# CO2SN.net
KiCad netlist of a schematic drawn in EAGLE
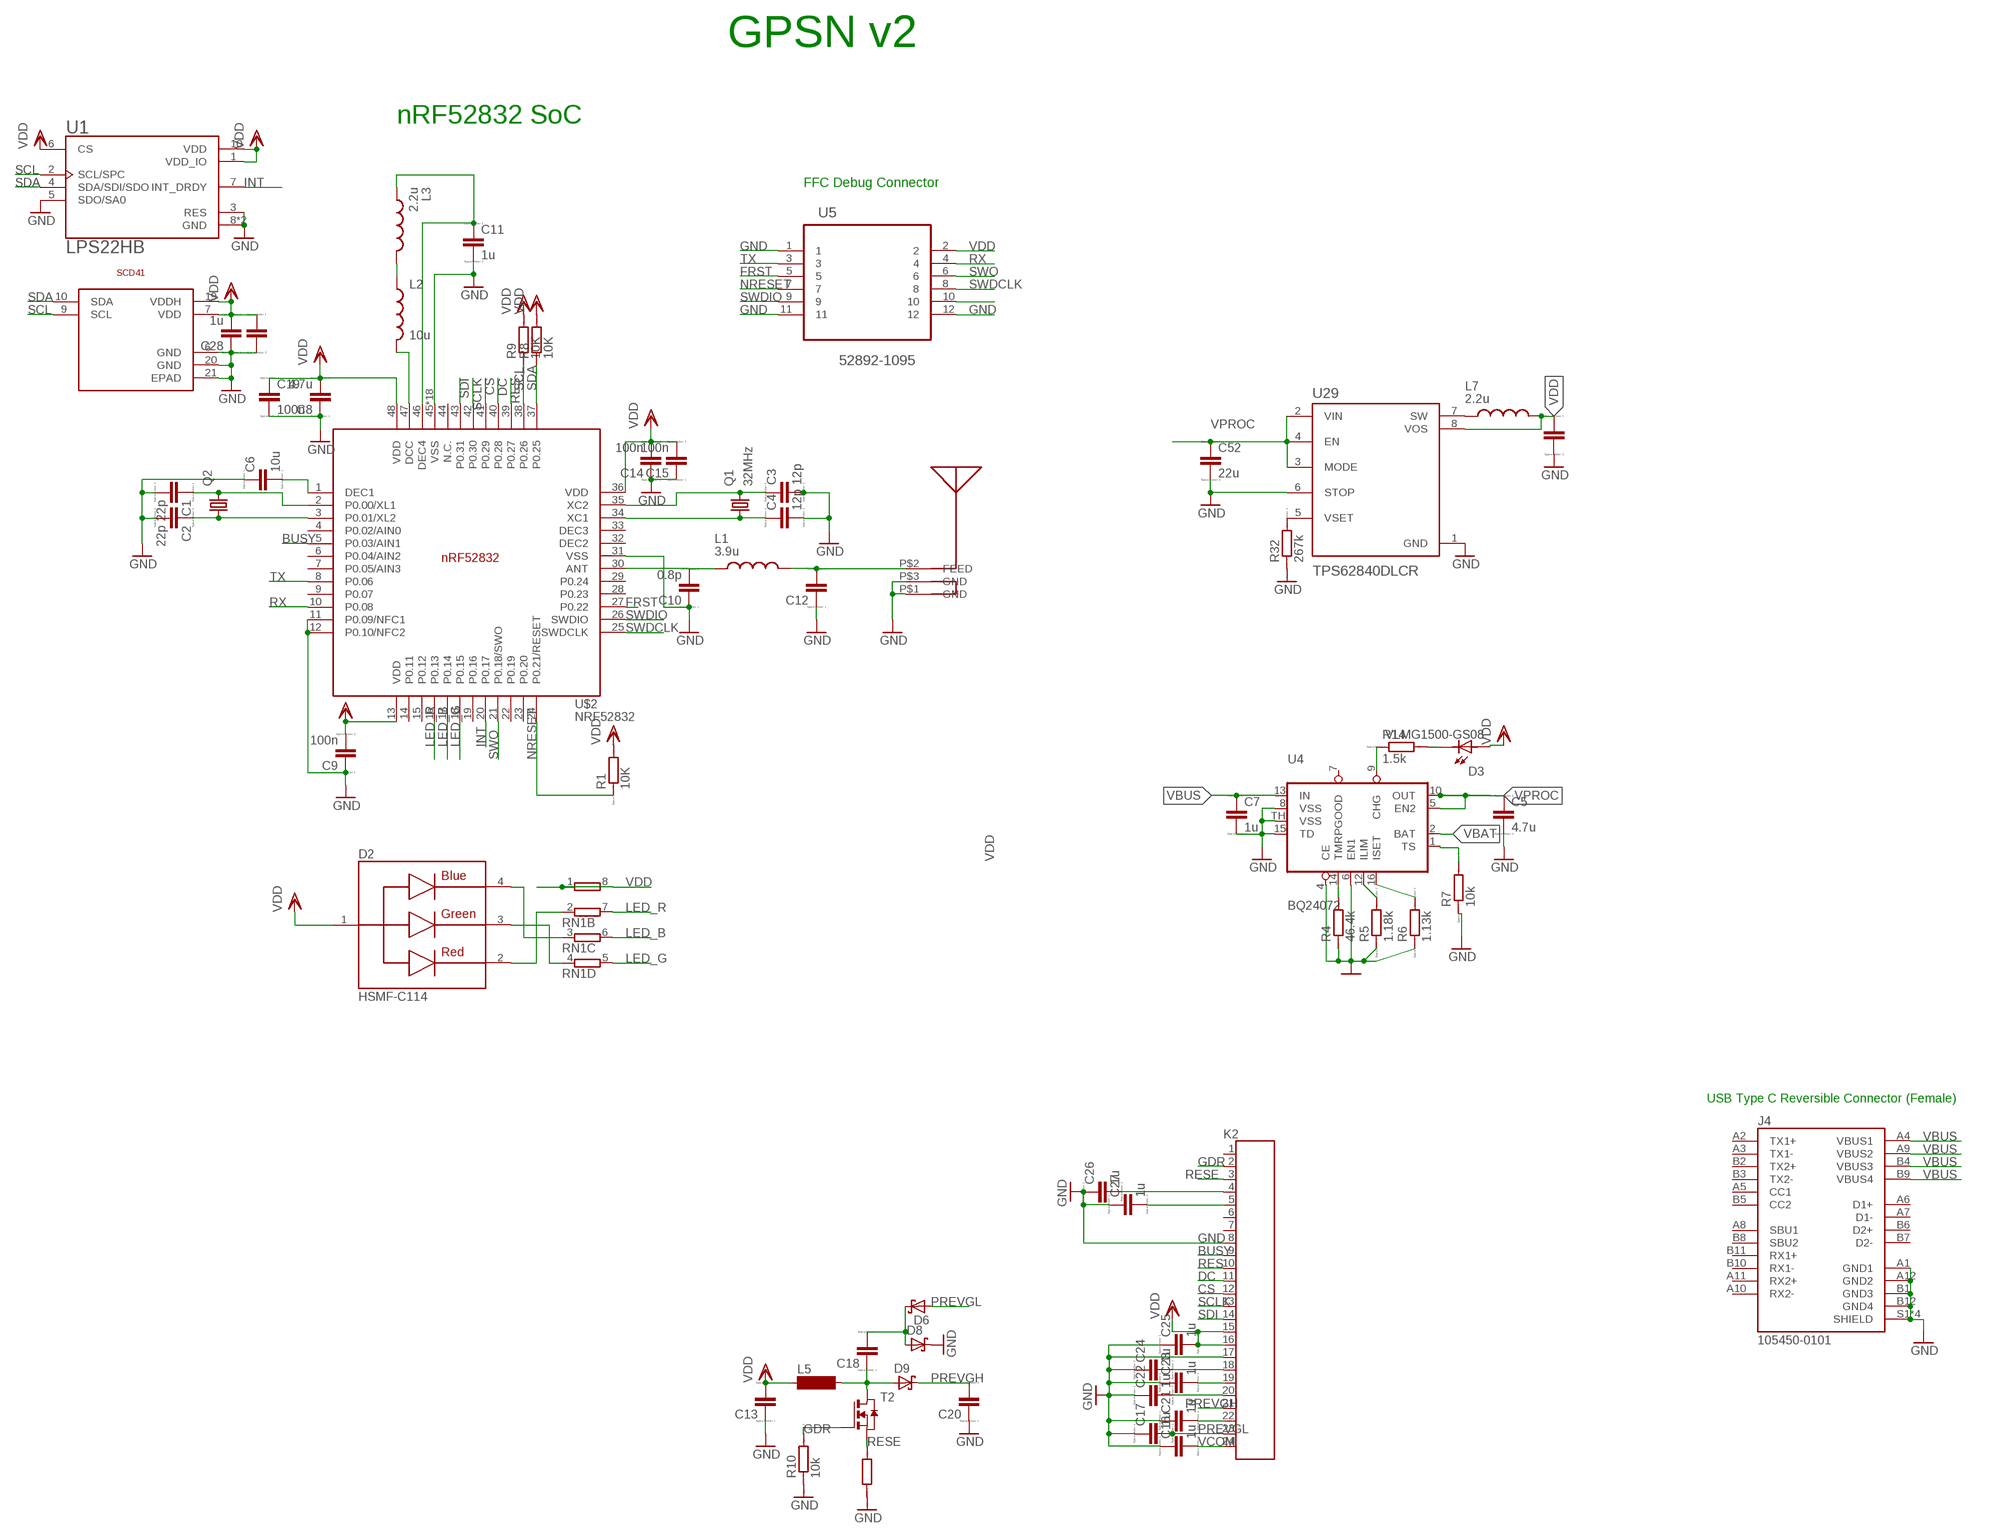
[diagram p0: schematic, sheet 1]

(export (version "E")
  (design (tool "Eeschema 10.0.6"))
  (components
    (comp (ref "C1")
      (value "22p")
      (footprint "eagle-import:C0402")
      (libsource (lib "eagle-import") (part "CC0402"))
    )
    (comp (ref "C2")
      (value "22p")
      (footprint "eagle-import:C0402")
      (libsource (lib "eagle-import") (part "CC0402"))
    )
    (comp (ref "C3")
      (value "12p")
      (footprint "eagle-import:C0402")
      (libsource (lib "eagle-import") (part "CC0402"))
    )
    (comp (ref "C4")
      (value "12p")
      (footprint "eagle-import:C0402")
      (libsource (lib "eagle-import") (part "CC0402"))
    )
    (comp (ref "C5")
      (value "4.7u")
      (footprint "eagle-import:C0402")
      (libsource (lib "eagle-import") (part "CC0402"))
    )
    (comp (ref "C6")
      (value "10u")
      (footprint "eagle-import:C0402")
      (libsource (lib "eagle-import") (part "CC0402"))
    )
    (comp (ref "C7")
      (value "1u")
      (footprint "eagle-import:C0402")
      (libsource (lib "eagle-import") (part "CC0402"))
    )
    (comp (ref "C8")
      (value "4.7u")
      (footprint "eagle-import:C0402")
      (libsource (lib "eagle-import") (part "CC0402"))
    )
    (comp (ref "C9")
      (value "100n")
      (footprint "eagle-import:C0603R")
      (libsource (lib "eagle-import") (part "CC0603R"))
    )
    (comp (ref "C10")
      (value "0.8p")
      (footprint "eagle-import:C0402")
      (libsource (lib "eagle-import") (part "CC0402"))
    )
    (comp (ref "C11")
      (value "1u")
      (footprint "eagle-import:C0402")
      (libsource (lib "eagle-import") (part "CC0402"))
    )
    (comp (ref "C12")
      (value "1.2p")
      (footprint "eagle-import:C0402")
      (libsource (lib "eagle-import") (part "CC0402"))
    )
    (comp (ref "C13")
      (value "100n")
      (footprint "eagle-import:C0603R")
      (libsource (lib "eagle-import") (part "CC0603R"))
    )
    (comp (ref "C14")
      (value "100n")
      (footprint "eagle-import:C0402")
      (libsource (lib "eagle-import") (part "CC0402"))
    )
    (comp (ref "C15")
      (value "100n")
      (footprint "eagle-import:C0402")
      (libsource (lib "eagle-import") (part "CC0402"))
    )
    (comp (ref "C16")
      (value "1u")
      (footprint "eagle-import:C0402")
      (libsource (lib "eagle-import") (part "CC0402"))
    )
    (comp (ref "C17")
      (value "1u")
      (footprint "eagle-import:C0402")
      (libsource (lib "eagle-import") (part "CC0402"))
    )
    (comp (ref "C18")
      (value "100n")
      (footprint "eagle-import:C0603R")
      (libsource (lib "eagle-import") (part "CC0603R"))
    )
    (comp (ref "C19")
      (value "100n")
      (footprint "eagle-import:C0402")
      (libsource (lib "eagle-import") (part "CC0402"))
    )
    (comp (ref "C20")
      (value "100n")
      (footprint "eagle-import:C0603R")
      (libsource (lib "eagle-import") (part "CC0603R"))
    )
    (comp (ref "C21")
      (value "1u")
      (footprint "eagle-import:C0402")
      (libsource (lib "eagle-import") (part "CC0402"))
    )
    (comp (ref "C22")
      (value "1u")
      (footprint "eagle-import:C0402")
      (libsource (lib "eagle-import") (part "CC0402"))
    )
    (comp (ref "C23")
      (value "1u")
      (footprint "eagle-import:C0402")
      (libsource (lib "eagle-import") (part "CC0402"))
    )
    (comp (ref "C24")
      (value "1u")
      (footprint "eagle-import:C0402")
      (libsource (lib "eagle-import") (part "CC0402"))
    )
    (comp (ref "C25")
      (value "1u")
      (footprint "eagle-import:C0402")
      (libsource (lib "eagle-import") (part "CC0402"))
    )
    (comp (ref "C26")
      (value "1u")
      (footprint "eagle-import:C0402")
      (libsource (lib "eagle-import") (part "CC0402"))
    )
    (comp (ref "C27")
      (value "1u")
      (footprint "eagle-import:C0402")
      (libsource (lib "eagle-import") (part "CC0402"))
    )
    (comp (ref "C28")
      (value "1u")
      (footprint "eagle-import:C0402")
      (libsource (lib "eagle-import") (part "CC0402"))
    )
    (comp (ref "C29")
      (value "22u")
      (footprint "eagle-import:C0603R")
      (libsource (lib "eagle-import") (part "CC0603R"))
    )
    (comp (ref "C52")
      (value "22u")
      (footprint "eagle-import:C0603R")
      (libsource (lib "eagle-import") (part "CC0603R"))
    )
    (comp (ref "C58")
      (value "22u")
      (footprint "eagle-import:C0603R")
      (libsource (lib "eagle-import") (part "CC0603R"))
    )
    (comp (ref "D2")
      (value "HSMF-C114")
      (footprint "eagle-import:DIOSC160X150X35-4N")
      (fields (field (name "MF") "Broadcom Limited"))
      (libsource (lib "eagle-import") (part "HSMF-C114"))
    )
    (comp (ref "D3")
      (value "VLMG1500-GS08")
      (footprint "eagle-import:LEDC1005X35N")
      (fields (field (name "MF") "Vishay"))
      (libsource (lib "eagle-import") (part "VLMG1500-GS08"))
    )
    (comp (ref "D6")
      (value "1PS79SB30,115")
      (footprint "eagle-import:SOD523")
      (fields (field (name "MF") "Nexperia"))
      (libsource (lib "eagle-import") (part "1PS79SB30,115"))
    )
    (comp (ref "D8")
      (value "1PS79SB30,115")
      (footprint "eagle-import:SOD523")
      (fields (field (name "MF") "Nexperia"))
      (libsource (lib "eagle-import") (part "1PS79SB30,115"))
    )
    (comp (ref "D9")
      (value "1PS79SB30,115")
      (footprint "eagle-import:SOD523")
      (fields (field (name "MF") "Nexperia"))
      (libsource (lib "eagle-import") (part "1PS79SB30,115"))
    )
    (comp (ref "J4")
      (value "105450-0101")
      (footprint "eagle-import:MOLEX_105450-0101")
      (fields (field (name "MF") "Molex") (field (name "MP") "1054500101"))
      (libsource (lib "eagle-import") (part "105450-0101"))
    )
    (comp (ref "K2")
      (value "687124149022")
      (footprint "eagle-import:687124149022")
      (fields (field (name "MF") "Wurth Electronics"))
      (libsource (lib "eagle-import") (part "687124149022"))
    )
    (comp (ref "L1")
      (value "3.9u")
      (footprint "eagle-import:INDC0402X26N")
      (fields (field (name "MF") "TDK") (field (name "MP") "MHQ0402P7N5JT000"))
      (libsource (lib "eagle-import") (part "MHQ0402P7N5JT000"))
    )
    (comp (ref "L2")
      (value "10u")
      (footprint "eagle-import:L0603")
      (libsource (lib "eagle-import") (part "INDUCTOR"))
    )
    (comp (ref "L3")
      (value "2.2u")
      (footprint "eagle-import:INDC0402X26N")
      (fields (field (name "MF") "TDK") (field (name "MP") "MHQ0402P7N5JT000"))
      (libsource (lib "eagle-import") (part "MHQ0402P7N5JT000"))
    )
    (comp (ref "L5")
      (value "SM-NE29")
      (footprint "eagle-import:SM-NE29")
      (libsource (lib "eagle-import") (part "SM-NE29"))
    )
    (comp (ref "L7")
      (value "2.2u")
      (footprint "eagle-import:INDC3225X120N")
      (fields (field (name "MF") "Murata") (field (name "MP") "1277AS-H-1R5M=P2"))
      (libsource (lib "eagle-import") (part "1277AS-H-1R5M=P2"))
    )
    (comp (ref "Q1")
      (value "32MHz")
      (footprint "eagle-import:2.0X1.6_KX-5")
      (libsource (lib "eagle-import") (part "KX-5"))
    )
    (comp (ref "Q2")
      (value "KX-327-RT")
      (footprint "eagle-import:2.0X1.2")
      (libsource (lib "eagle-import") (part "KX-327-RT"))
    )
    (comp (ref "R1")
      (value "10K")
      (footprint "eagle-import:R0402")
      (libsource (lib "eagle-import") (part "RR0402"))
    )
    (comp (ref "R4")
      (value "46.4k")
      (footprint "eagle-import:R0402")
      (libsource (lib "eagle-import") (part "RR0402"))
    )
    (comp (ref "R5")
      (value "1.18k")
      (footprint "eagle-import:R0402")
      (libsource (lib "eagle-import") (part "RR0402"))
    )
    (comp (ref "R6")
      (value "1.13k")
      (footprint "eagle-import:R0402")
      (libsource (lib "eagle-import") (part "RR0402"))
    )
    (comp (ref "R7")
      (value "10k")
      (footprint "eagle-import:R0402")
      (libsource (lib "eagle-import") (part "RR0402"))
    )
    (comp (ref "R8")
      (value "10K")
      (footprint "eagle-import:R0402")
      (libsource (lib "eagle-import") (part "RR0402"))
    )
    (comp (ref "R9")
      (value "10K")
      (footprint "eagle-import:R0402")
      (libsource (lib "eagle-import") (part "RR0402"))
    )
    (comp (ref "R10")
      (value "10k")
      (footprint "eagle-import:R0402")
      (libsource (lib "eagle-import") (part "RR0402"))
    )
    (comp (ref "R11")
      (value "0.47")
      (footprint "eagle-import:R0402")
      (libsource (lib "eagle-import") (part "RR0402"))
    )
    (comp (ref "R14")
      (value "1.5k")
      (footprint "eagle-import:R0402")
      (libsource (lib "eagle-import") (part "RR0402"))
    )
    (comp (ref "R32")
      (value "267k")
      (footprint "eagle-import:R0402")
      (libsource (lib "eagle-import") (part "RR0402"))
    )
    (comp (ref "RN1")
      (value "4R-N0402ARV341")
      (footprint "eagle-import:4X0402ARV341")
      (libsource (lib "eagle-import") (part "4R-N0402ARV341"))
    )
    (comp (ref "T2")
      (value "NMOSSOT23")
      (footprint "eagle-import:SOT-23")
      (libsource (lib "eagle-import") (part "NMOSSOT23"))
    )
    (comp (ref "U$1")
      (value "SCD41")
      (footprint "eagle-import:SCD41")
      (libsource (lib "eagle-import") (part "SCD41"))
    )
    (comp (ref "U$2")
      (value "NRF52832")
      (footprint "eagle-import:QFN40P600X600X90-48_N")
      (libsource (lib "eagle-import") (part "NRF52832"))
    )
    (comp (ref "U$4")
      (value "CHIPANTENNAL2")
      (footprint "eagle-import:CHIPANTENNAL2")
      (libsource (lib "eagle-import") (part "CHIPANTENNAL2"))
    )
    (comp (ref "U1")
      (value "LPS22HB")
      (footprint "eagle-import:LGA10R50P2X3_200X200X80")
      (fields (field (name "MF") "STMicroelectronics"))
      (libsource (lib "eagle-import") (part "LPS22HB"))
    )
    (comp (ref "U4")
      (value "BQ24072")
      (footprint "eagle-import:S-PVQFN-N16")
      (libsource (lib "eagle-import") (part "BQ24072"))
    )
    (comp (ref "U5")
      (value "52892-1095")
      (footprint "eagle-import:MOLEX_52892-1095")
      (fields (field (name "MF") "Molex"))
      (libsource (lib "eagle-import") (part "52892-1095"))
    )
    (comp (ref "U29")
      (value "TPS62840DLCR")
      (footprint "eagle-import:SON50P200X150X100-8N")
      (fields (field (name "MF") "Texas Instruments"))
      (libsource (lib "eagle-import") (part "TPS62840DLCR"))
    )
  )
  (nets
    (net (code "1") (name "/BUSY") (class "Default")
      (node (ref "K2") (pin "9") (pinfunction "9_9") (pintype "passive"))
      (node (ref "U$2") (pin "5") (pinfunction "P0.03/AIN1_5") (pintype "bidirectional"))
    )
    (net (code "2") (name "/CS") (class "Default")
      (node (ref "K2") (pin "12") (pinfunction "12_12") (pintype "passive"))
      (node (ref "U$2") (pin "41") (pinfunction "P0.29_41") (pintype "bidirectional"))
    )
    (net (code "3") (name "/DC") (class "Default")
      (node (ref "K2") (pin "11") (pinfunction "11_11") (pintype "passive"))
      (node (ref "U$2") (pin "40") (pinfunction "P0.28_40") (pintype "bidirectional"))
    )
    (net (code "4") (name "/FRST") (class "Default")
      (node (ref "U$2") (pin "27") (pinfunction "P0.22_27") (pintype "bidirectional"))
      (node (ref "U5") (pin "5") (pinfunction "5_5") (pintype "passive"))
    )
    (net (code "5") (name "/GDR") (class "Default")
      (node (ref "K2") (pin "2") (pinfunction "2_2") (pintype "passive"))
      (node (ref "R10") (pin "2") (pinfunction "2_2") (pintype "passive"))
      (node (ref "T2") (pin "3") (pinfunction "G_3") (pintype "passive"))
    )
    (net (code "6") (name "/INT") (class "Default")
      (node (ref "U$2") (pin "20") (pinfunction "P0.17_20") (pintype "bidirectional"))
      (node (ref "U1") (pin "7") (pinfunction "INT_DRDY_7") (pintype "output"))
    )
    (net (code "7") (name "/LED_B") (class "Default")
      (node (ref "RN1") (pin "6") (pinfunction "2_6") (pintype "passive"))
      (node (ref "U$2") (pin "17") (pinfunction "P0.14_17") (pintype "bidirectional"))
    )
    (net (code "8") (name "/LED_G") (class "Default")
      (node (ref "RN1") (pin "5") (pinfunction "2_5") (pintype "passive"))
      (node (ref "U$2") (pin "18") (pinfunction "P0.15_18") (pintype "bidirectional"))
    )
    (net (code "9") (name "/LED_R") (class "Default")
      (node (ref "RN1") (pin "7") (pinfunction "2_7") (pintype "passive"))
      (node (ref "U$2") (pin "16") (pinfunction "P0.13_16") (pintype "bidirectional"))
    )
    (net (code "10") (name "/NRESET") (class "Default")
      (node (ref "R1") (pin "1") (pinfunction "1_1") (pintype "passive"))
      (node (ref "U$2") (pin "24") (pinfunction "P0.21/RESET_24") (pintype "bidirectional"))
      (node (ref "U5") (pin "7") (pinfunction "7_7") (pintype "passive"))
    )
    (net (code "11") (name "/PREVGH") (class "Default")
      (node (ref "C20") (pin "2") (pinfunction "2_2") (pintype "passive"))
      (node (ref "D9") (pin "1") (pinfunction "K_1") (pintype "passive"))
      (node (ref "K2") (pin "21") (pinfunction "21_21") (pintype "passive"))
    )
    (net (code "12") (name "/PREVGL") (class "Default")
      (node (ref "C17") (pin "2") (pinfunction "2_2") (pintype "passive"))
      (node (ref "D6") (pin "2") (pinfunction "A_2") (pintype "passive"))
      (node (ref "K2") (pin "23") (pinfunction "23_23") (pintype "passive"))
    )
    (net (code "13") (name "/RES") (class "Default")
      (node (ref "K2") (pin "10") (pinfunction "10_10") (pintype "passive"))
      (node (ref "U$2") (pin "39") (pinfunction "P0.27_39") (pintype "bidirectional"))
    )
    (net (code "14") (name "/RESE") (class "Default")
      (node (ref "K2") (pin "3") (pinfunction "3_3") (pintype "passive"))
      (node (ref "R11") (pin "2") (pinfunction "2_2") (pintype "passive"))
      (node (ref "T2") (pin "2") (pinfunction "S_2") (pintype "passive"))
    )
    (net (code "15") (name "/RX") (class "Default")
      (node (ref "U$2") (pin "10") (pinfunction "P0.08_10") (pintype "bidirectional"))
      (node (ref "U5") (pin "4") (pinfunction "4_4") (pintype "passive"))
    )
    (net (code "16") (name "/SCL") (class "Default")
      (node (ref "R9") (pin "1") (pinfunction "1_1") (pintype "passive"))
      (node (ref "U$1") (pin "9") (pinfunction "SCL_9") (pintype "bidirectional"))
      (node (ref "U$2") (pin "38") (pinfunction "P0.26_38") (pintype "bidirectional"))
      (node (ref "U1") (pin "2") (pinfunction "SCL/SPC_2") (pintype "input"))
    )
    (net (code "17") (name "/SCLK") (class "Default")
      (node (ref "K2") (pin "13") (pinfunction "13_13") (pintype "passive"))
      (node (ref "U$2") (pin "42") (pinfunction "P0.30_42") (pintype "bidirectional"))
    )
    (net (code "18") (name "/SDA") (class "Default")
      (node (ref "R8") (pin "1") (pinfunction "1_1") (pintype "passive"))
      (node (ref "U$1") (pin "10") (pinfunction "SDA_10") (pintype "bidirectional"))
      (node (ref "U$2") (pin "37") (pinfunction "P0.25_37") (pintype "bidirectional"))
      (node (ref "U1") (pin "4") (pinfunction "SDA/SDI/SDO_4") (pintype "bidirectional"))
    )
    (net (code "19") (name "/SDI") (class "Default")
      (node (ref "K2") (pin "14") (pinfunction "14_14") (pintype "passive"))
      (node (ref "U$2") (pin "43") (pinfunction "P0.31_43") (pintype "bidirectional"))
    )
    (net (code "20") (name "/SWDCLK") (class "Default")
      (node (ref "U$2") (pin "25") (pinfunction "SWDCLK_25") (pintype "input"))
      (node (ref "U5") (pin "8") (pinfunction "8_8") (pintype "passive"))
    )
    (net (code "21") (name "/SWDIO") (class "Default")
      (node (ref "U$2") (pin "26") (pinfunction "SWDIO_26") (pintype "bidirectional"))
      (node (ref "U5") (pin "9") (pinfunction "9_9") (pintype "passive"))
    )
    (net (code "22") (name "/SWO") (class "Default")
      (node (ref "U$2") (pin "21") (pinfunction "P0.18/SWO_21") (pintype "bidirectional"))
      (node (ref "U5") (pin "6") (pinfunction "6_6") (pintype "passive"))
    )
    (net (code "23") (name "/TX") (class "Default")
      (node (ref "U$2") (pin "8") (pinfunction "P0.06_8") (pintype "bidirectional"))
      (node (ref "U5") (pin "3") (pinfunction "3_3") (pintype "passive"))
    )
    (net (code "24") (name "/VCOM") (class "Default")
      (node (ref "C16") (pin "2") (pinfunction "2_2") (pintype "passive"))
      (node (ref "K2") (pin "24") (pinfunction "24_24") (pintype "passive"))
    )
    (net (code "25") (name "GND") (class "Default")
      (node (ref "C1") (pin "2") (pinfunction "2_2") (pintype "passive"))
      (node (ref "C10") (pin "1") (pinfunction "1_1") (pintype "passive"))
      (node (ref "C11") (pin "2") (pinfunction "2_2") (pintype "passive"))
      (node (ref "C12") (pin "1") (pinfunction "1_1") (pintype "passive"))
      (node (ref "C13") (pin "1") (pinfunction "1_1") (pintype "passive"))
      (node (ref "C14") (pin "1") (pinfunction "1_1") (pintype "passive"))
      (node (ref "C15") (pin "1") (pinfunction "1_1") (pintype "passive"))
      (node (ref "C16") (pin "1") (pinfunction "1_1") (pintype "passive"))
      (node (ref "C17") (pin "1") (pinfunction "1_1") (pintype "passive"))
      (node (ref "C19") (pin "2") (pinfunction "2_2") (pintype "passive"))
      (node (ref "C2") (pin "2") (pinfunction "2_2") (pintype "passive"))
      (node (ref "C20") (pin "1") (pinfunction "1_1") (pintype "passive"))
      (node (ref "C21") (pin "1") (pinfunction "1_1") (pintype "passive"))
      (node (ref "C22") (pin "1") (pinfunction "1_1") (pintype "passive"))
      (node (ref "C23") (pin "1") (pinfunction "1_1") (pintype "passive"))
      (node (ref "C24") (pin "1") (pinfunction "1_1") (pintype "passive"))
      (node (ref "C25") (pin "1") (pinfunction "1_1") (pintype "passive"))
      (node (ref "C26") (pin "1") (pinfunction "1_1") (pintype "passive"))
      (node (ref "C27") (pin "1") (pinfunction "1_1") (pintype "passive"))
      (node (ref "C28") (pin "1") (pinfunction "1_1") (pintype "passive"))
      (node (ref "C29") (pin "2") (pinfunction "2_2") (pintype "passive"))
      (node (ref "C3") (pin "2") (pinfunction "2_2") (pintype "passive"))
      (node (ref "C4") (pin "2") (pinfunction "2_2") (pintype "passive"))
      (node (ref "C5") (pin "2") (pinfunction "2_2") (pintype "passive"))
      (node (ref "C52") (pin "2") (pinfunction "2_2") (pintype "passive"))
      (node (ref "C58") (pin "2") (pinfunction "2_2") (pintype "passive"))
      (node (ref "C6") (pin "1") (pinfunction "1_1") (pintype "passive"))
      (node (ref "C7") (pin "2") (pinfunction "2_2") (pintype "passive"))
      (node (ref "C8") (pin "1") (pinfunction "1_1") (pintype "passive"))
      (node (ref "C9") (pin "1") (pinfunction "1_1") (pintype "passive"))
      (node (ref "D8") (pin "1") (pinfunction "K_1") (pintype "passive"))
      (node (ref "J4") (pin "A1") (pinfunction "GND1_A1") (pintype "passive"))
      (node (ref "J4") (pin "A12") (pinfunction "GND2_A12") (pintype "passive"))
      (node (ref "J4") (pin "B1") (pinfunction "GND3_B1") (pintype "passive"))
      (node (ref "J4") (pin "B12") (pinfunction "GND4_B12") (pintype "passive"))
      (node (ref "J4") (pin "S1") (pinfunction "SHIELD_S1") (pintype "passive"))
      (node (ref "J4") (pin "S2") (pinfunction "SHIELD_S2") (pintype "passive"))
      (node (ref "J4") (pin "S3") (pinfunction "SHIELD_S3") (pintype "passive"))
      (node (ref "J4") (pin "S4") (pinfunction "SHIELD_S4") (pintype "passive"))
      (node (ref "K2") (pin "17") (pinfunction "17_17") (pintype "passive"))
      (node (ref "K2") (pin "8") (pinfunction "8_8") (pintype "passive"))
      (node (ref "R10") (pin "1") (pinfunction "1_1") (pintype "passive"))
      (node (ref "R11") (pin "1") (pinfunction "1_1") (pintype "passive"))
      (node (ref "R32") (pin "1") (pinfunction "1_1") (pintype "passive"))
      (node (ref "R4") (pin "1") (pinfunction "1_1") (pintype "passive"))
      (node (ref "R5") (pin "1") (pinfunction "1_1") (pintype "passive"))
      (node (ref "R6") (pin "1") (pinfunction "1_1") (pintype "passive"))
      (node (ref "R7") (pin "1") (pinfunction "1_1") (pintype "passive"))
      (node (ref "U$1") (pin "20") (pinfunction "GND_20") (pintype "bidirectional"))
      (node (ref "U$1") (pin "21") (pinfunction "EPAD_21") (pintype "bidirectional"))
      (node (ref "U$1") (pin "6") (pinfunction "GND_6") (pintype "bidirectional"))
      (node (ref "U$2") (pin "11") (pinfunction "P0.09/NFC1_11") (pintype "bidirectional"))
      (node (ref "U$2") (pin "12") (pinfunction "P0.10/NFC2_12") (pintype "bidirectional"))
      (node (ref "U$2") (pin "31") (pinfunction "VSS_31") (pintype "bidirectional"))
      (node (ref "U$2") (pin "45") (pinfunction "VSS_45") (pintype "power_in"))
      (node (ref "U$2") (pin "PAD") (pinfunction "VSS_PAD") (pintype "power_in"))
      (node (ref "U$2") (pin "PAD@VIA01") (pinfunction "VSS_PAD@VIA01") (pintype "power_in"))
      (node (ref "U$2") (pin "PAD@VIA02") (pinfunction "VSS_PAD@VIA02") (pintype "power_in"))
      (node (ref "U$2") (pin "PAD@VIA03") (pinfunction "VSS_PAD@VIA03") (pintype "power_in"))
      (node (ref "U$2") (pin "PAD@VIA04") (pinfunction "VSS_PAD@VIA04") (pintype "power_in"))
      (node (ref "U$2") (pin "PAD@VIA05") (pinfunction "VSS_PAD@VIA05") (pintype "power_in"))
      (node (ref "U$2") (pin "PAD@VIA06") (pinfunction "VSS_PAD@VIA06") (pintype "power_in"))
      (node (ref "U$2") (pin "PAD@VIA07") (pinfunction "VSS_PAD@VIA07") (pintype "power_in"))
      (node (ref "U$2") (pin "PAD@VIA08") (pinfunction "VSS_PAD@VIA08") (pintype "power_in"))
      (node (ref "U$2") (pin "PAD@VIA09") (pinfunction "VSS_PAD@VIA09") (pintype "power_in"))
      (node (ref "U$2") (pin "PAD@VIA10") (pinfunction "VSS_PAD@VIA10") (pintype "power_in"))
      (node (ref "U$2") (pin "PAD@VIA11") (pinfunction "VSS_PAD@VIA11") (pintype "power_in"))
      (node (ref "U$2") (pin "PAD@VIA12") (pinfunction "VSS_PAD@VIA12") (pintype "power_in"))
      (node (ref "U$2") (pin "PAD@VIA13") (pinfunction "VSS_PAD@VIA13") (pintype "power_in"))
      (node (ref "U$2") (pin "PAD@VIA14") (pinfunction "VSS_PAD@VIA14") (pintype "power_in"))
      (node (ref "U$2") (pin "PAD@VIA15") (pinfunction "VSS_PAD@VIA15") (pintype "power_in"))
      (node (ref "U$2") (pin "PAD@VIA16") (pinfunction "VSS_PAD@VIA16") (pintype "power_in"))
      (node (ref "U$4") (pin "P$1") (pinfunction "GND_P$1") (pintype "bidirectional"))
      (node (ref "U$4") (pin "P$3") (pinfunction "GND_P$3") (pintype "bidirectional"))
      (node (ref "U1") (pin "3") (pinfunction "RES_3") (pintype "power_in"))
      (node (ref "U1") (pin "5") (pinfunction "SDO/SA0_5") (pintype "bidirectional"))
      (node (ref "U1") (pin "8") (pinfunction "GND_8") (pintype "power_in"))
      (node (ref "U1") (pin "9") (pinfunction "GND_9") (pintype "power_in"))
      (node (ref "U29") (pin "1") (pinfunction "GND_1") (pintype "power_in"))
      (node (ref "U29") (pin "6") (pinfunction "STOP_6") (pintype "input"))
      (node (ref "U4") (pin "15") (pinfunction "TD_15") (pintype "bidirectional"))
      (node (ref "U4") (pin "4") (pinfunction "CE_4") (pintype "bidirectional"))
      (node (ref "U4") (pin "6") (pinfunction "EN1_6") (pintype "bidirectional"))
      (node (ref "U4") (pin "8") (pinfunction "VSS_8") (pintype "power_in"))
      (node (ref "U4") (pin "TH") (pinfunction "VSS_TH") (pintype "power_in"))
      (node (ref "U5") (pin "1") (pinfunction "1_1") (pintype "passive"))
      (node (ref "U5") (pin "11") (pinfunction "11_11") (pintype "passive"))
      (node (ref "U5") (pin "12") (pinfunction "12_12") (pintype "passive"))
    )
    (net (code "26") (name "Net-(C21-Pad2)") (class "Default")
      (node (ref "C21") (pin "2") (pinfunction "2_2") (pintype "passive"))
      (node (ref "K2") (pin "22") (pinfunction "22_22") (pintype "passive"))
    )
    (net (code "27") (name "Net-(C22-Pad2)") (class "Default")
      (node (ref "C22") (pin "2") (pinfunction "2_2") (pintype "passive"))
      (node (ref "K2") (pin "20") (pinfunction "20_20") (pintype "passive"))
    )
    (net (code "28") (name "Net-(C23-Pad2)") (class "Default")
      (node (ref "C23") (pin "2") (pinfunction "2_2") (pintype "passive"))
      (node (ref "K2") (pin "19") (pinfunction "19_19") (pintype "passive"))
    )
    (net (code "29") (name "Net-(C24-Pad2)") (class "Default")
      (node (ref "C24") (pin "2") (pinfunction "2_2") (pintype "passive"))
      (node (ref "K2") (pin "18") (pinfunction "18_18") (pintype "passive"))
    )
    (net (code "30") (name "Net-(C26-Pad2)") (class "Default")
      (node (ref "C26") (pin "2") (pinfunction "2_2") (pintype "passive"))
      (node (ref "K2") (pin "4") (pinfunction "4_4") (pintype "passive"))
    )
    (net (code "31") (name "Net-(C27-Pad2)") (class "Default")
      (node (ref "C27") (pin "2") (pinfunction "2_2") (pintype "passive"))
      (node (ref "K2") (pin "5") (pinfunction "5_5") (pintype "passive"))
    )
    (net (code "32") (name "Net-(D3-Pad2)") (class "Default")
      (node (ref "D3") (pin "2") (pinfunction "2_2") (pintype "passive"))
      (node (ref "R14") (pin "2") (pinfunction "2_2") (pintype "passive"))
    )
    (net (code "33") (name "Net-(D6-K)") (class "Default")
      (node (ref "C18") (pin "2") (pinfunction "2_2") (pintype "passive"))
      (node (ref "D6") (pin "1") (pinfunction "K_1") (pintype "passive"))
      (node (ref "D8") (pin "2") (pinfunction "A_2") (pintype "passive"))
    )
    (net (code "34") (name "Net-(D9-A)") (class "Default")
      (node (ref "C18") (pin "1") (pinfunction "1_1") (pintype "passive"))
      (node (ref "D9") (pin "2") (pinfunction "A_2") (pintype "passive"))
      (node (ref "L5") (pin "2") (pinfunction "2_2") (pintype "passive"))
      (node (ref "T2") (pin "1") (pinfunction "D_1") (pintype "passive"))
    )
    (net (code "35") (name "Net-(L2-Pad1)") (class "Default")
      (node (ref "L2") (pin "1") (pinfunction "1_1") (pintype "passive"))
      (node (ref "L3") (pin "2") (pinfunction "2_2") (pintype "passive"))
    )
    (net (code "36") (name "Net-(Q1-2)") (class "Default")
      (node (ref "C3") (pin "1") (pinfunction "1_1") (pintype "passive"))
      (node (ref "Q1") (pin "3") (pinfunction "2_3") (pintype "passive"))
      (node (ref "U$2") (pin "35") (pinfunction "XC2_35") (pintype "output"))
    )
    (net (code "37") (name "Net-(RN1B-1)") (class "Default")
      (node (ref "D2") (pin "2") (pinfunction "2_2") (pintype "passive"))
      (node (ref "RN1") (pin "2") (pinfunction "1_2") (pintype "passive"))
    )
    (net (code "38") (name "Net-(RN1C-1)") (class "Default")
      (node (ref "D2") (pin "4") (pinfunction "4_4") (pintype "passive"))
      (node (ref "RN1") (pin "3") (pinfunction "1_3") (pintype "passive"))
    )
    (net (code "39") (name "Net-(RN1D-1)") (class "Default")
      (node (ref "D2") (pin "3") (pinfunction "3_3") (pintype "passive"))
      (node (ref "RN1") (pin "4") (pinfunction "1_4") (pintype "passive"))
    )
    (net (code "40") (name "Net-(U$2-ANT)") (class "Default")
      (node (ref "C10") (pin "2") (pinfunction "2_2") (pintype "passive"))
      (node (ref "L1") (pin "1") (pinfunction "1_1") (pintype "passive"))
      (node (ref "U$2") (pin "30") (pinfunction "ANT_30") (pintype "bidirectional"))
    )
    (net (code "41") (name "Net-(U$2-DCC)") (class "Default")
      (node (ref "L2") (pin "2") (pinfunction "2_2") (pintype "passive"))
      (node (ref "U$2") (pin "47") (pinfunction "DCC_47") (pintype "output"))
    )
    (net (code "42") (name "Net-(U$2-DEC1)") (class "Default")
      (node (ref "C6") (pin "2") (pinfunction "2_2") (pintype "passive"))
      (node (ref "U$2") (pin "1") (pinfunction "DEC1_1") (pintype "power_in"))
    )
    (net (code "43") (name "Net-(U$2-DEC4)") (class "Default")
      (node (ref "C11") (pin "1") (pinfunction "1_1") (pintype "passive"))
      (node (ref "L3") (pin "1") (pinfunction "1_1") (pintype "passive"))
      (node (ref "U$2") (pin "46") (pinfunction "DEC4_46") (pintype "power_in"))
    )
    (net (code "44") (name "Net-(U$2-P0.00{slash}XL1)") (class "Default")
      (node (ref "C1") (pin "1") (pinfunction "1_1") (pintype "passive"))
      (node (ref "Q2") (pin "2") (pinfunction "2_2") (pintype "passive"))
      (node (ref "U$2") (pin "2") (pinfunction "P0.00/XL1_2") (pintype "bidirectional"))
    )
    (net (code "45") (name "Net-(U$2-P0.01{slash}XL2)") (class "Default")
      (node (ref "C2") (pin "1") (pinfunction "1_1") (pintype "passive"))
      (node (ref "Q2") (pin "1") (pinfunction "1_1") (pintype "passive"))
      (node (ref "U$2") (pin "3") (pinfunction "P0.01/XL2_3") (pintype "bidirectional"))
    )
    (net (code "46") (name "Net-(U$2-XC1)") (class "Default")
      (node (ref "C4") (pin "1") (pinfunction "1_1") (pintype "passive"))
      (node (ref "Q1") (pin "1") (pinfunction "1_1") (pintype "passive"))
      (node (ref "U$2") (pin "34") (pinfunction "XC1_34") (pintype "input"))
    )
    (net (code "47") (name "Net-(U$4-FEED)") (class "Default")
      (node (ref "C12") (pin "2") (pinfunction "2_2") (pintype "passive"))
      (node (ref "L1") (pin "2") (pinfunction "2_2") (pintype "passive"))
      (node (ref "U$4") (pin "P$2") (pinfunction "FEED_P$2") (pintype "bidirectional"))
    )
    (net (code "48") (name "Net-(U4-CHG)") (class "Default")
      (node (ref "R14") (pin "1") (pinfunction "1_1") (pintype "passive"))
      (node (ref "U4") (pin "9") (pinfunction "CHG_9") (pintype "bidirectional"))
    )
    (net (code "49") (name "Net-(U4-ILIM)") (class "Default")
      (node (ref "R5") (pin "2") (pinfunction "2_2") (pintype "passive"))
      (node (ref "U4") (pin "12") (pinfunction "ILIM_12") (pintype "bidirectional"))
    )
    (net (code "50") (name "Net-(U4-ISET)") (class "Default")
      (node (ref "R6") (pin "2") (pinfunction "2_2") (pintype "passive"))
      (node (ref "U4") (pin "16") (pinfunction "ISET_16") (pintype "input"))
    )
    (net (code "51") (name "Net-(U4-TMR)") (class "Default")
      (node (ref "R4") (pin "2") (pinfunction "2_2") (pintype "passive"))
      (node (ref "U4") (pin "14") (pinfunction "TMR_14") (pintype "bidirectional"))
    )
    (net (code "52") (name "Net-(U4-TS)") (class "Default")
      (node (ref "R7") (pin "2") (pinfunction "2_2") (pintype "passive"))
      (node (ref "U4") (pin "1") (pinfunction "TS_1") (pintype "input"))
    )
    (net (code "53") (name "Net-(U29-SW)") (class "Default")
      (node (ref "L7") (pin "1") (pinfunction "1_1") (pintype "passive"))
      (node (ref "U29") (pin "7") (pinfunction "SW_7") (pintype "power_in"))
    )
    (net (code "54") (name "Net-(U29-VSET)") (class "Default")
      (node (ref "R32") (pin "2") (pinfunction "2_2") (pintype "passive"))
      (node (ref "U29") (pin "5") (pinfunction "VSET_5") (pintype "input"))
    )
    (net (code "55") (name "VBAT") (class "Default")
      (node (ref "U4") (pin "2") (pinfunction "BAT_2") (pintype "input"))
    )
    (net (code "56") (name "VBUS") (class "Default")
      (node (ref "C7") (pin "1") (pinfunction "1_1") (pintype "passive"))
      (node (ref "J4") (pin "A4") (pinfunction "VBUS1_A4") (pintype "passive"))
      (node (ref "J4") (pin "A9") (pinfunction "VBUS2_A9") (pintype "passive"))
      (node (ref "J4") (pin "B4") (pinfunction "VBUS3_B4") (pintype "passive"))
      (node (ref "J4") (pin "B9") (pinfunction "VBUS4_B9") (pintype "passive"))
      (node (ref "U4") (pin "13") (pinfunction "IN_13") (pintype "input"))
    )
    (net (code "57") (name "VDD") (class "Default")
      (node (ref "C13") (pin "2") (pinfunction "2_2") (pintype "passive"))
      (node (ref "C14") (pin "2") (pinfunction "2_2") (pintype "passive"))
      (node (ref "C15") (pin "2") (pinfunction "2_2") (pintype "passive"))
      (node (ref "C19") (pin "1") (pinfunction "1_1") (pintype "passive"))
      (node (ref "C25") (pin "2") (pinfunction "2_2") (pintype "passive"))
      (node (ref "C28") (pin "2") (pinfunction "2_2") (pintype "passive"))
      (node (ref "C29") (pin "1") (pinfunction "1_1") (pintype "passive"))
      (node (ref "C58") (pin "1") (pinfunction "1_1") (pintype "passive"))
      (node (ref "C8") (pin "2") (pinfunction "2_2") (pintype "passive"))
      (node (ref "C9") (pin "2") (pinfunction "2_2") (pintype "passive"))
      (node (ref "D2") (pin "1") (pinfunction "1_1") (pintype "passive"))
      (node (ref "D3") (pin "1") (pinfunction "1_1") (pintype "passive"))
      (node (ref "K2") (pin "15") (pinfunction "15_15") (pintype "passive"))
      (node (ref "K2") (pin "16") (pinfunction "16_16") (pintype "passive"))
      (node (ref "L5") (pin "1") (pinfunction "1_1") (pintype "passive"))
      (node (ref "L7") (pin "2") (pinfunction "2_2") (pintype "passive"))
      (node (ref "R1") (pin "2") (pinfunction "2_2") (pintype "passive"))
      (node (ref "R8") (pin "2") (pinfunction "2_2") (pintype "passive"))
      (node (ref "R9") (pin "2") (pinfunction "2_2") (pintype "passive"))
      (node (ref "RN1") (pin "1") (pinfunction "1_1") (pintype "passive"))
      (node (ref "RN1") (pin "8") (pinfunction "2_8") (pintype "passive"))
      (node (ref "U$1") (pin "19") (pinfunction "VDDH_19") (pintype "bidirectional"))
      (node (ref "U$1") (pin "7") (pinfunction "VDD_7") (pintype "bidirectional"))
      (node (ref "U$2") (pin "13") (pinfunction "VDD_13") (pintype "power_in"))
      (node (ref "U$2") (pin "36") (pinfunction "VDD_36") (pintype "power_in"))
      (node (ref "U$2") (pin "48") (pinfunction "VDD_48") (pintype "power_in"))
      (node (ref "U1") (pin "1") (pinfunction "VDD_IO_1") (pintype "power_in"))
      (node (ref "U1") (pin "10") (pinfunction "VDD_10") (pintype "power_in"))
      (node (ref "U1") (pin "6") (pinfunction "CS_6") (pintype "input"))
      (node (ref "U29") (pin "8") (pinfunction "VOS_8") (pintype "input"))
      (node (ref "U5") (pin "2") (pinfunction "2_2") (pintype "passive"))
    )
    (net (code "58") (name "VPROC") (class "Default")
      (node (ref "C5") (pin "1") (pinfunction "1_1") (pintype "passive"))
      (node (ref "C52") (pin "1") (pinfunction "1_1") (pintype "passive"))
      (node (ref "U29") (pin "2") (pinfunction "VIN_2") (pintype "power_in"))
      (node (ref "U29") (pin "3") (pinfunction "MODE_3") (pintype "input"))
      (node (ref "U29") (pin "4") (pinfunction "EN_4") (pintype "input"))
      (node (ref "U4") (pin "10") (pinfunction "OUT_10") (pintype "output"))
      (node (ref "U4") (pin "5") (pinfunction "EN2_5") (pintype "input"))
    )
    (net (code "59") (name "unconnected-(J4-CC1-PadA5)") (class "Default")
      (node (ref "J4") (pin "A5") (pinfunction "CC1_A5") (pintype "passive"))
    )
    (net (code "60") (name "unconnected-(J4-CC2-PadB5)") (class "Default")
      (node (ref "J4") (pin "B5") (pinfunction "CC2_B5") (pintype "passive"))
    )
    (net (code "61") (name "unconnected-(J4-D1+-PadA6)") (class "Default")
      (node (ref "J4") (pin "A6") (pinfunction "D1+_A6") (pintype "passive"))
    )
    (net (code "62") (name "unconnected-(J4-D1--PadA7)") (class "Default")
      (node (ref "J4") (pin "A7") (pinfunction "D1-_A7") (pintype "passive"))
    )
    (net (code "63") (name "unconnected-(J4-D2+-PadB6)") (class "Default")
      (node (ref "J4") (pin "B6") (pinfunction "D2+_B6") (pintype "passive"))
    )
    (net (code "64") (name "unconnected-(J4-D2--PadB7)") (class "Default")
      (node (ref "J4") (pin "B7") (pinfunction "D2-_B7") (pintype "passive"))
    )
    (net (code "65") (name "unconnected-(J4-RX1+-PadB11)") (class "Default")
      (node (ref "J4") (pin "B11") (pinfunction "RX1+_B11") (pintype "passive"))
    )
    (net (code "66") (name "unconnected-(J4-RX1--PadB10)") (class "Default")
      (node (ref "J4") (pin "B10") (pinfunction "RX1-_B10") (pintype "passive"))
    )
    (net (code "67") (name "unconnected-(J4-RX2+-PadA11)") (class "Default")
      (node (ref "J4") (pin "A11") (pinfunction "RX2+_A11") (pintype "passive"))
    )
    (net (code "68") (name "unconnected-(J4-RX2--PadA10)") (class "Default")
      (node (ref "J4") (pin "A10") (pinfunction "RX2-_A10") (pintype "passive"))
    )
    (net (code "69") (name "unconnected-(J4-SBU1-PadA8)") (class "Default")
      (node (ref "J4") (pin "A8") (pinfunction "SBU1_A8") (pintype "passive"))
    )
    (net (code "70") (name "unconnected-(J4-SBU2-PadB8)") (class "Default")
      (node (ref "J4") (pin "B8") (pinfunction "SBU2_B8") (pintype "passive"))
    )
    (net (code "71") (name "unconnected-(J4-TX1+-PadA2)") (class "Default")
      (node (ref "J4") (pin "A2") (pinfunction "TX1+_A2") (pintype "passive"))
    )
    (net (code "72") (name "unconnected-(J4-TX1--PadA3)") (class "Default")
      (node (ref "J4") (pin "A3") (pinfunction "TX1-_A3") (pintype "passive"))
    )
    (net (code "73") (name "unconnected-(J4-TX2+-PadB2)") (class "Default")
      (node (ref "J4") (pin "B2") (pinfunction "TX2+_B2") (pintype "passive"))
    )
    (net (code "74") (name "unconnected-(J4-TX2--PadB3)") (class "Default")
      (node (ref "J4") (pin "B3") (pinfunction "TX2-_B3") (pintype "passive"))
    )
    (net (code "75") (name "unconnected-(K2-Pad1)") (class "Default")
      (node (ref "K2") (pin "1") (pinfunction "1_1") (pintype "passive"))
    )
    (net (code "76") (name "unconnected-(K2-Pad6)") (class "Default")
      (node (ref "K2") (pin "6") (pinfunction "6_6") (pintype "passive"))
    )
    (net (code "77") (name "unconnected-(K2-Pad7)") (class "Default")
      (node (ref "K2") (pin "7") (pinfunction "7_7") (pintype "passive"))
    )
    (net (code "78") (name "unconnected-(U$2-DEC2-Pad32)") (class "Default")
      (node (ref "U$2") (pin "32") (pinfunction "DEC2_32") (pintype "bidirectional"))
    )
    (net (code "79") (name "unconnected-(U$2-DEC3-Pad33)") (class "Default")
      (node (ref "U$2") (pin "33") (pinfunction "DEC3_33") (pintype "bidirectional"))
    )
    (net (code "80") (name "unconnected-(U$2-N.C.-Pad44)") (class "Default")
      (node (ref "U$2") (pin "44") (pinfunction "N.C._44") (pintype "no_connect"))
    )
    (net (code "81") (name "unconnected-(U$2-P0.02{slash}AIN0-Pad4)") (class "Default")
      (node (ref "U$2") (pin "4") (pinfunction "P0.02/AIN0_4") (pintype "bidirectional"))
    )
    (net (code "82") (name "unconnected-(U$2-P0.04{slash}AIN2-Pad6)") (class "Default")
      (node (ref "U$2") (pin "6") (pinfunction "P0.04/AIN2_6") (pintype "bidirectional"))
    )
    (net (code "83") (name "unconnected-(U$2-P0.05{slash}AIN3-Pad7)") (class "Default")
      (node (ref "U$2") (pin "7") (pinfunction "P0.05/AIN3_7") (pintype "bidirectional"))
    )
    (net (code "84") (name "unconnected-(U$2-P0.07-Pad9)") (class "Default")
      (node (ref "U$2") (pin "9") (pinfunction "P0.07_9") (pintype "bidirectional"))
    )
    (net (code "85") (name "unconnected-(U$2-P0.11-Pad14)") (class "Default")
      (node (ref "U$2") (pin "14") (pinfunction "P0.11_14") (pintype "bidirectional"))
    )
    (net (code "86") (name "unconnected-(U$2-P0.12-Pad15)") (class "Default")
      (node (ref "U$2") (pin "15") (pinfunction "P0.12_15") (pintype "bidirectional"))
    )
    (net (code "87") (name "unconnected-(U$2-P0.16-Pad19)") (class "Default")
      (node (ref "U$2") (pin "19") (pinfunction "P0.16_19") (pintype "bidirectional"))
    )
    (net (code "88") (name "unconnected-(U$2-P0.19-Pad22)") (class "Default")
      (node (ref "U$2") (pin "22") (pinfunction "P0.19_22") (pintype "bidirectional"))
    )
    (net (code "89") (name "unconnected-(U$2-P0.20-Pad23)") (class "Default")
      (node (ref "U$2") (pin "23") (pinfunction "P0.20_23") (pintype "bidirectional"))
    )
    (net (code "90") (name "unconnected-(U$2-P0.23-Pad28)") (class "Default")
      (node (ref "U$2") (pin "28") (pinfunction "P0.23_28") (pintype "bidirectional"))
    )
    (net (code "91") (name "unconnected-(U$2-P0.24-Pad29)") (class "Default")
      (node (ref "U$2") (pin "29") (pinfunction "P0.24_29") (pintype "bidirectional"))
    )
    (net (code "92") (name "unconnected-(U4-PGOOD-Pad7)") (class "Default")
      (node (ref "U4") (pin "7") (pinfunction "PGOOD_7") (pintype "bidirectional"))
    )
    (net (code "93") (name "unconnected-(U5-Pad10)") (class "Default")
      (node (ref "U5") (pin "10") (pinfunction "10_10") (pintype "passive"))
    )
  )
)
